# SDI12IB_v0_5.net
KiCad netlist of a schematic drawn in EAGLE
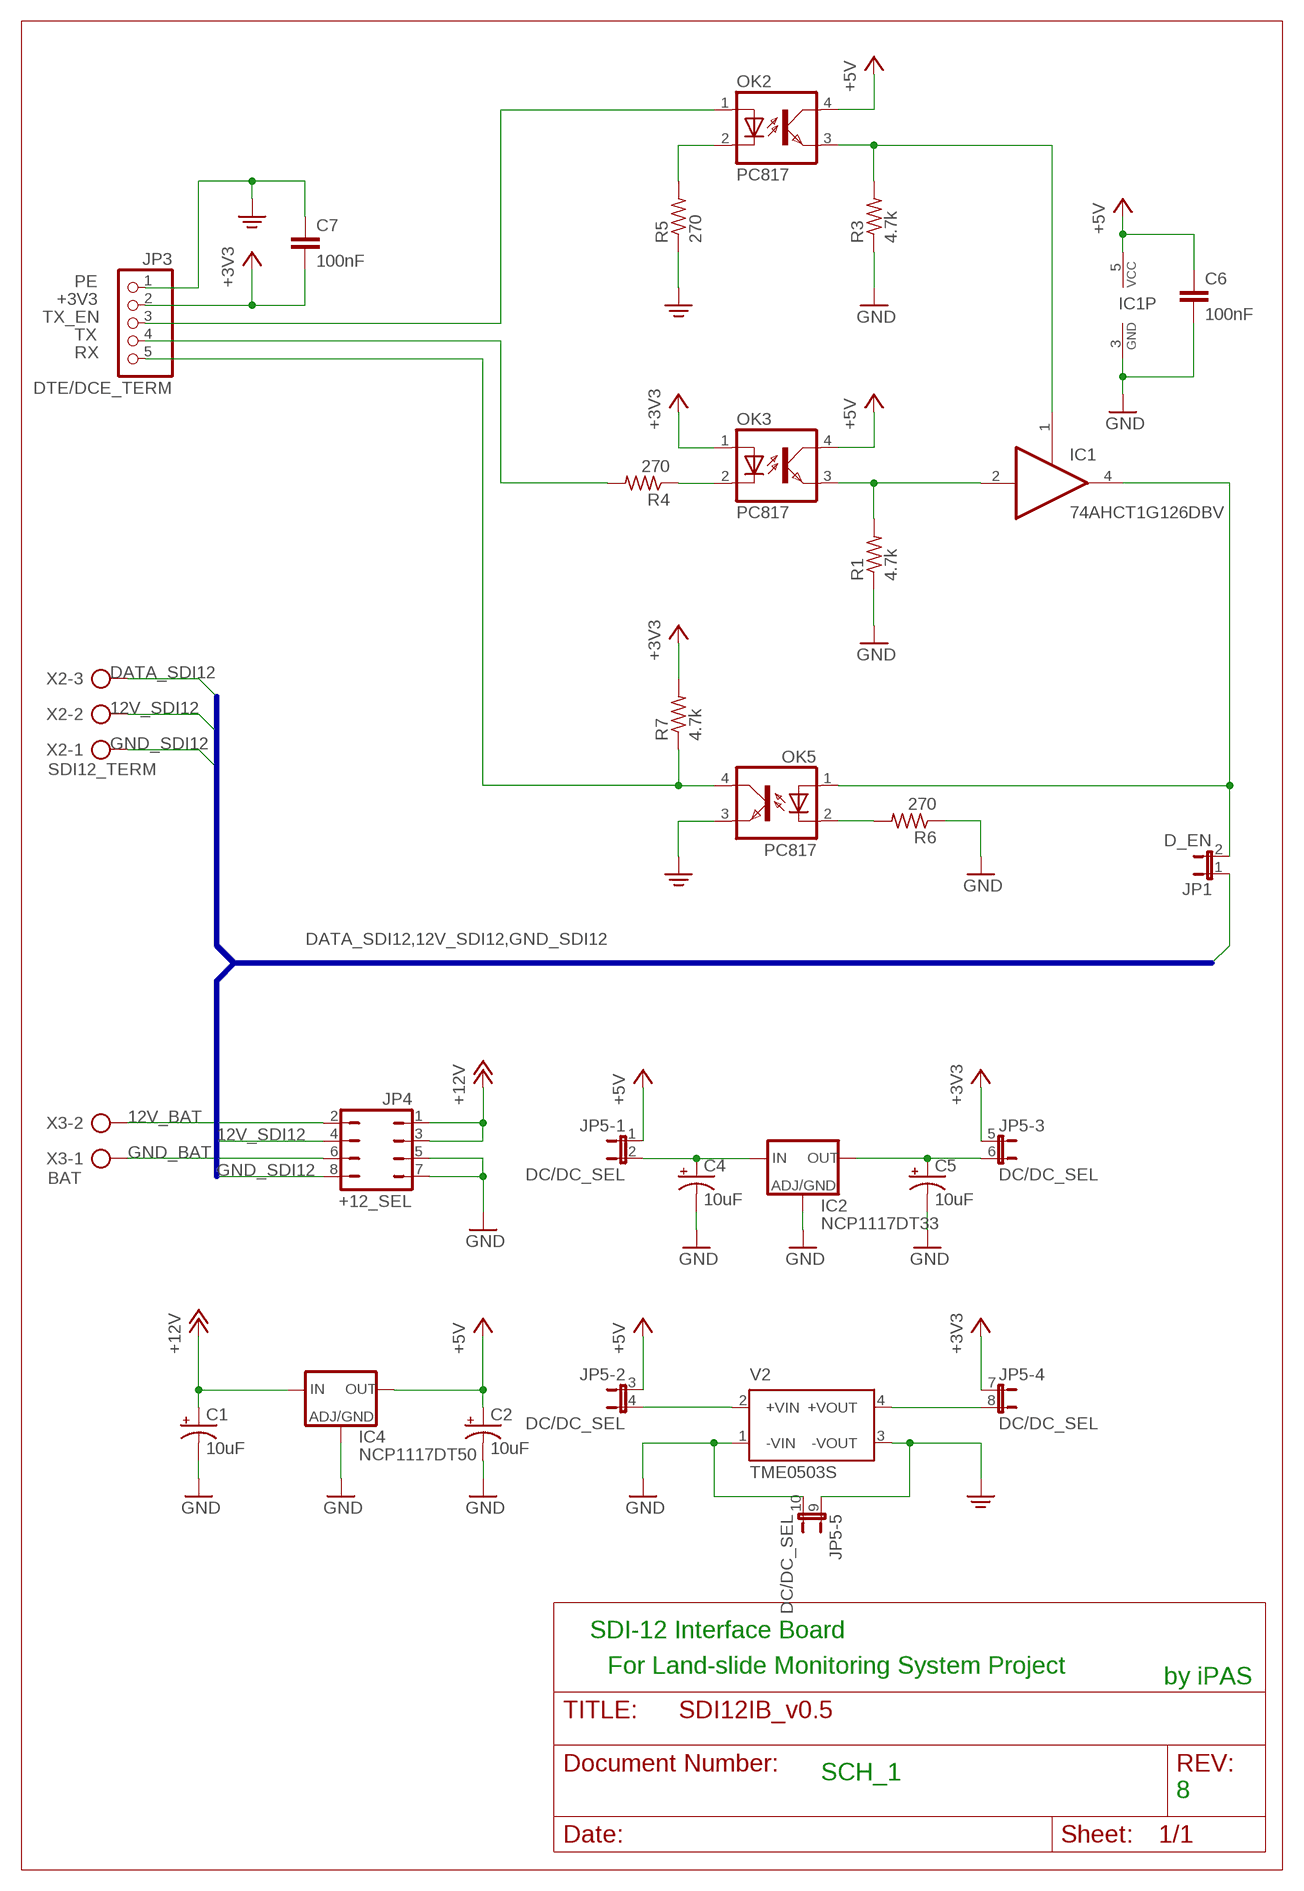
[diagram p0: schematic, sheet 1]

(export (version "E")
  (design (tool "Eeschema 10.0.6"))
  (components
    (comp (ref "C1")
      (value "10uF")
      (footprint "eagle-import:E2-5")
      (libsource (lib "eagle-import") (part "CPOL-USE2-5"))
    )
    (comp (ref "C2")
      (value "10uF")
      (footprint "eagle-import:E2-5")
      (libsource (lib "eagle-import") (part "CPOL-USE2-5"))
    )
    (comp (ref "C4")
      (value "10uF")
      (footprint "eagle-import:E2-5")
      (libsource (lib "eagle-import") (part "CPOL-USE2-5"))
    )
    (comp (ref "C5")
      (value "10uF")
      (footprint "eagle-import:E2-5")
      (libsource (lib "eagle-import") (part "CPOL-USE2-5"))
    )
    (comp (ref "C6")
      (value "100nF")
      (footprint "eagle-import:C1210")
      (libsource (lib "eagle-import") (part "C-EUC1210"))
    )
    (comp (ref "C7")
      (value "100nF")
      (footprint "eagle-import:C050-025X075")
      (libsource (lib "eagle-import") (part "C-EU050-025X075"))
    )
    (comp (ref "IC1")
      (value "74AHCT1G126DBV")
      (footprint "eagle-import:SOT23-5")
      (libsource (lib "eagle-import") (part "741G126DBVAHCT"))
    )
    (comp (ref "IC2")
      (value "NCP1117DT33")
      (footprint "eagle-import:DPACK")
      (libsource (lib "eagle-import") (part "NCP1117?DT33"))
    )
    (comp (ref "IC4")
      (value "NCP1117DT50")
      (footprint "eagle-import:DPACK")
      (libsource (lib "eagle-import") (part "NCP1117?DT50"))
    )
    (comp (ref "JP1")
      (value "D_EN")
      (footprint "eagle-import:JP1")
      (libsource (lib "eagle-import") (part "JP1E"))
    )
    (comp (ref "JP3")
      (value "DTE/DCE_TERM")
      (footprint "eagle-import:1X05")
      (libsource (lib "eagle-import") (part "PINHD-1X5"))
    )
    (comp (ref "JP4")
      (value "+12_SEL")
      (footprint "eagle-import:JP4Q")
      (libsource (lib "eagle-import") (part "JP4Q"))
    )
    (comp (ref "JP5")
      (value "DC/DC_SEL")
      (footprint "eagle-import:JP5Q")
      (libsource (lib "eagle-import") (part "JP5QE"))
    )
    (comp (ref "OK2")
      (value "PC817")
      (footprint "eagle-import:DIL04")
      (fields (field (name "MPN") "PC817X4J000F"))
      (libsource (lib "eagle-import") (part "PC817"))
    )
    (comp (ref "OK3")
      (value "PC817")
      (footprint "eagle-import:DIL04")
      (fields (field (name "MPN") "PC817X4J000F"))
      (libsource (lib "eagle-import") (part "PC817"))
    )
    (comp (ref "OK5")
      (value "PC817")
      (footprint "eagle-import:DIL04")
      (fields (field (name "MPN") "PC817X4J000F"))
      (libsource (lib "eagle-import") (part "PC817"))
    )
    (comp (ref "R1")
      (value "4.7k")
      (footprint "eagle-import:0204_7")
      (libsource (lib "eagle-import") (part "R-US_0204/7"))
    )
    (comp (ref "R3")
      (value "4.7k")
      (footprint "eagle-import:0204_7")
      (libsource (lib "eagle-import") (part "R-US_0204/7"))
    )
    (comp (ref "R4")
      (value "270")
      (footprint "eagle-import:0204_7")
      (libsource (lib "eagle-import") (part "R-US_0204/7"))
    )
    (comp (ref "R5")
      (value "270")
      (footprint "eagle-import:0204_7")
      (libsource (lib "eagle-import") (part "R-US_0204/7"))
    )
    (comp (ref "R6")
      (value "270")
      (footprint "eagle-import:0204_7")
      (libsource (lib "eagle-import") (part "R-US_0204/7"))
    )
    (comp (ref "R7")
      (value "4.7k")
      (footprint "eagle-import:0204_7")
      (libsource (lib "eagle-import") (part "R-US_0204/7"))
    )
    (comp (ref "V2")
      (value "TME0503S")
      (footprint "eagle-import:TME")
      (fields (field (name "MPN") "TME 0503S"))
      (libsource (lib "eagle-import") (part "TME?0503S"))
    )
    (comp (ref "X2")
      (value "SDI12_TERM")
      (footprint "eagle-import:AK300_3")
      (libsource (lib "eagle-import") (part "AK300/3"))
    )
    (comp (ref "X3")
      (value "BAT")
      (footprint "eagle-import:AK300_2")
      (libsource (lib "eagle-import") (part "AK300/2"))
    )
  )
  (nets
    (net (code "1") (name "+3V3") (class "Default")
      (node (ref "C7") (pin "2") (pinfunction "2_2") (pintype "passive"))
      (node (ref "JP3") (pin "2") (pinfunction "2_2") (pintype "passive"))
      (node (ref "JP5") (pin "5") (pinfunction "1_5") (pintype "passive"))
      (node (ref "JP5") (pin "7") (pinfunction "1_7") (pintype "passive"))
      (node (ref "OK3") (pin "1") (pinfunction "A_1") (pintype "passive"))
      (node (ref "R7") (pin "2") (pinfunction "2_2") (pintype "passive"))
    )
    (net (code "2") (name "+5V") (class "Default")
      (node (ref "C2") (pin "+") (pinfunction "+_+") (pintype "passive"))
      (node (ref "C6") (pin "1") (pinfunction "1_1") (pintype "passive"))
      (node (ref "IC1") (pin "5") (pinfunction "VCC_5") (pintype "power_in"))
      (node (ref "IC4") (pin "4") (pinfunction "OUT_4") (pintype "passive"))
      (node (ref "JP5") (pin "1") (pinfunction "1_1") (pintype "passive"))
      (node (ref "JP5") (pin "3") (pinfunction "1_3") (pintype "passive"))
      (node (ref "OK2") (pin "4") (pinfunction "COL_4") (pintype "passive"))
      (node (ref "OK3") (pin "4") (pinfunction "COL_4") (pintype "passive"))
    )
    (net (code "3") (name "+12V") (class "Default")
      (node (ref "C1") (pin "+") (pinfunction "+_+") (pintype "passive"))
      (node (ref "IC4") (pin "3") (pinfunction "IN_3") (pintype "input"))
      (node (ref "JP4") (pin "1") (pinfunction "1_1") (pintype "passive"))
      (node (ref "JP4") (pin "3") (pinfunction "3_3") (pintype "passive"))
    )
    (net (code "4") (name "/12V_BAT") (class "Default")
      (node (ref "JP4") (pin "2") (pinfunction "2_2") (pintype "passive"))
      (node (ref "X3") (pin "2") (pinfunction "KL_2") (pintype "passive"))
    )
    (net (code "5") (name "/12V_SDI12") (class "Default")
      (node (ref "JP4") (pin "4") (pinfunction "4_4") (pintype "passive"))
      (node (ref "X2") (pin "2") (pinfunction "KL_2") (pintype "passive"))
    )
    (net (code "6") (name "/DATA_SDI12") (class "Default")
      (node (ref "JP1") (pin "1") (pinfunction "1_1") (pintype "passive"))
      (node (ref "X2") (pin "3") (pinfunction "KL_3") (pintype "passive"))
    )
    (net (code "7") (name "/GND_BAT") (class "Default")
      (node (ref "JP4") (pin "6") (pinfunction "6_6") (pintype "passive"))
      (node (ref "X3") (pin "1") (pinfunction "KL_1") (pintype "passive"))
    )
    (net (code "8") (name "/GND_SDI12") (class "Default")
      (node (ref "JP4") (pin "8") (pinfunction "8_8") (pintype "passive"))
      (node (ref "X2") (pin "1") (pinfunction "KL_1") (pintype "passive"))
    )
    (net (code "9") (name "/RX") (class "Default")
      (node (ref "JP3") (pin "5") (pinfunction "5_5") (pintype "passive"))
      (node (ref "OK5") (pin "4") (pinfunction "COL_4") (pintype "passive"))
      (node (ref "R7") (pin "1") (pinfunction "1_1") (pintype "passive"))
    )
    (net (code "10") (name "/TX") (class "Default")
      (node (ref "JP3") (pin "4") (pinfunction "4_4") (pintype "passive"))
      (node (ref "R4") (pin "2") (pinfunction "2_2") (pintype "passive"))
    )
    (net (code "11") (name "/TX_EN") (class "Default")
      (node (ref "JP3") (pin "3") (pinfunction "3_3") (pintype "passive"))
      (node (ref "OK2") (pin "1") (pinfunction "A_1") (pintype "passive"))
    )
    (net (code "13") (name "GND") (class "Default")
      (node (ref "C1") (pin "-") (pinfunction "-_-") (pintype "passive"))
      (node (ref "C2") (pin "-") (pinfunction "-_-") (pintype "passive"))
      (node (ref "C4") (pin "-") (pinfunction "-_-") (pintype "passive"))
      (node (ref "C5") (pin "-") (pinfunction "-_-") (pintype "passive"))
      (node (ref "C6") (pin "2") (pinfunction "2_2") (pintype "passive"))
      (node (ref "IC1") (pin "3") (pinfunction "GND_3") (pintype "power_in"))
      (node (ref "IC2") (pin "1") (pinfunction "ADJ_1") (pintype "input"))
      (node (ref "IC4") (pin "1") (pinfunction "ADJ_1") (pintype "input"))
      (node (ref "JP4") (pin "5") (pinfunction "5_5") (pintype "passive"))
      (node (ref "JP4") (pin "7") (pinfunction "7_7") (pintype "passive"))
      (node (ref "JP5") (pin "10") (pinfunction "2_10") (pintype "passive"))
      (node (ref "R1") (pin "1") (pinfunction "1_1") (pintype "passive"))
      (node (ref "R3") (pin "1") (pinfunction "1_1") (pintype "passive"))
      (node (ref "R6") (pin "1") (pinfunction "1_1") (pintype "passive"))
      (node (ref "V2") (pin "1") (pinfunction "-VIN_1") (pintype "passive"))
    )
    (net (code "14") (name "Net-(IC1A-I)") (class "Default")
      (node (ref "IC1") (pin "2") (pinfunction "I_2") (pintype "input"))
      (node (ref "OK3") (pin "3") (pinfunction "EMIT_3") (pintype "passive"))
      (node (ref "R1") (pin "2") (pinfunction "2_2") (pintype "passive"))
    )
    (net (code "15") (name "Net-(IC1A-O)") (class "Default")
      (node (ref "IC1") (pin "4") (pinfunction "O_4") (pintype "output"))
      (node (ref "JP1") (pin "2") (pinfunction "2_2") (pintype "passive"))
      (node (ref "OK5") (pin "1") (pinfunction "A_1") (pintype "passive"))
    )
    (net (code "16") (name "Net-(IC1A-OE)") (class "Default")
      (node (ref "IC1") (pin "1") (pinfunction "OE_1") (pintype "input"))
      (node (ref "OK2") (pin "3") (pinfunction "EMIT_3") (pintype "passive"))
      (node (ref "R3") (pin "2") (pinfunction "2_2") (pintype "passive"))
    )
    (net (code "17") (name "Net-(IC2-IN)") (class "Default")
      (node (ref "C4") (pin "+") (pinfunction "+_+") (pintype "passive"))
      (node (ref "IC2") (pin "3") (pinfunction "IN_3") (pintype "input"))
      (node (ref "JP5") (pin "2") (pinfunction "2_2") (pintype "passive"))
    )
    (net (code "18") (name "Net-(IC2-OUT)") (class "Default")
      (node (ref "C5") (pin "+") (pinfunction "+_+") (pintype "passive"))
      (node (ref "IC2") (pin "4") (pinfunction "OUT_4") (pintype "passive"))
      (node (ref "JP5") (pin "6") (pinfunction "2_6") (pintype "passive"))
    )
    (net (code "19") (name "Net-(JP5B-2)") (class "Default")
      (node (ref "JP5") (pin "4") (pinfunction "2_4") (pintype "passive"))
      (node (ref "V2") (pin "2") (pinfunction "+VIN_2") (pintype "passive"))
    )
    (net (code "20") (name "Net-(JP5D-2)") (class "Default")
      (node (ref "JP5") (pin "8") (pinfunction "2_8") (pintype "passive"))
      (node (ref "V2") (pin "4") (pinfunction "+VOUT_4") (pintype "passive"))
    )
    (net (code "21") (name "Net-(OK2-C)") (class "Default")
      (node (ref "OK2") (pin "2") (pinfunction "C_2") (pintype "passive"))
      (node (ref "R5") (pin "2") (pinfunction "2_2") (pintype "passive"))
    )
    (net (code "22") (name "Net-(OK3-C)") (class "Default")
      (node (ref "OK3") (pin "2") (pinfunction "C_2") (pintype "passive"))
      (node (ref "R4") (pin "1") (pinfunction "1_1") (pintype "passive"))
    )
    (net (code "23") (name "Net-(OK5-C)") (class "Default")
      (node (ref "OK5") (pin "2") (pinfunction "C_2") (pintype "passive"))
      (node (ref "R6") (pin "2") (pinfunction "2_2") (pintype "passive"))
    )
    (net (code "24") (name "PE") (class "Default")
      (node (ref "C7") (pin "1") (pinfunction "1_1") (pintype "passive"))
      (node (ref "JP3") (pin "1") (pinfunction "1_1") (pintype "passive"))
      (node (ref "JP5") (pin "9") (pinfunction "1_9") (pintype "passive"))
      (node (ref "OK5") (pin "3") (pinfunction "EMIT_3") (pintype "passive"))
      (node (ref "R5") (pin "1") (pinfunction "1_1") (pintype "passive"))
      (node (ref "V2") (pin "3") (pinfunction "-VOUT_3") (pintype "passive"))
    )
  )
)
